# VBATTSecondary.net
KiCad netlist of a schematic drawn in Altium Designer
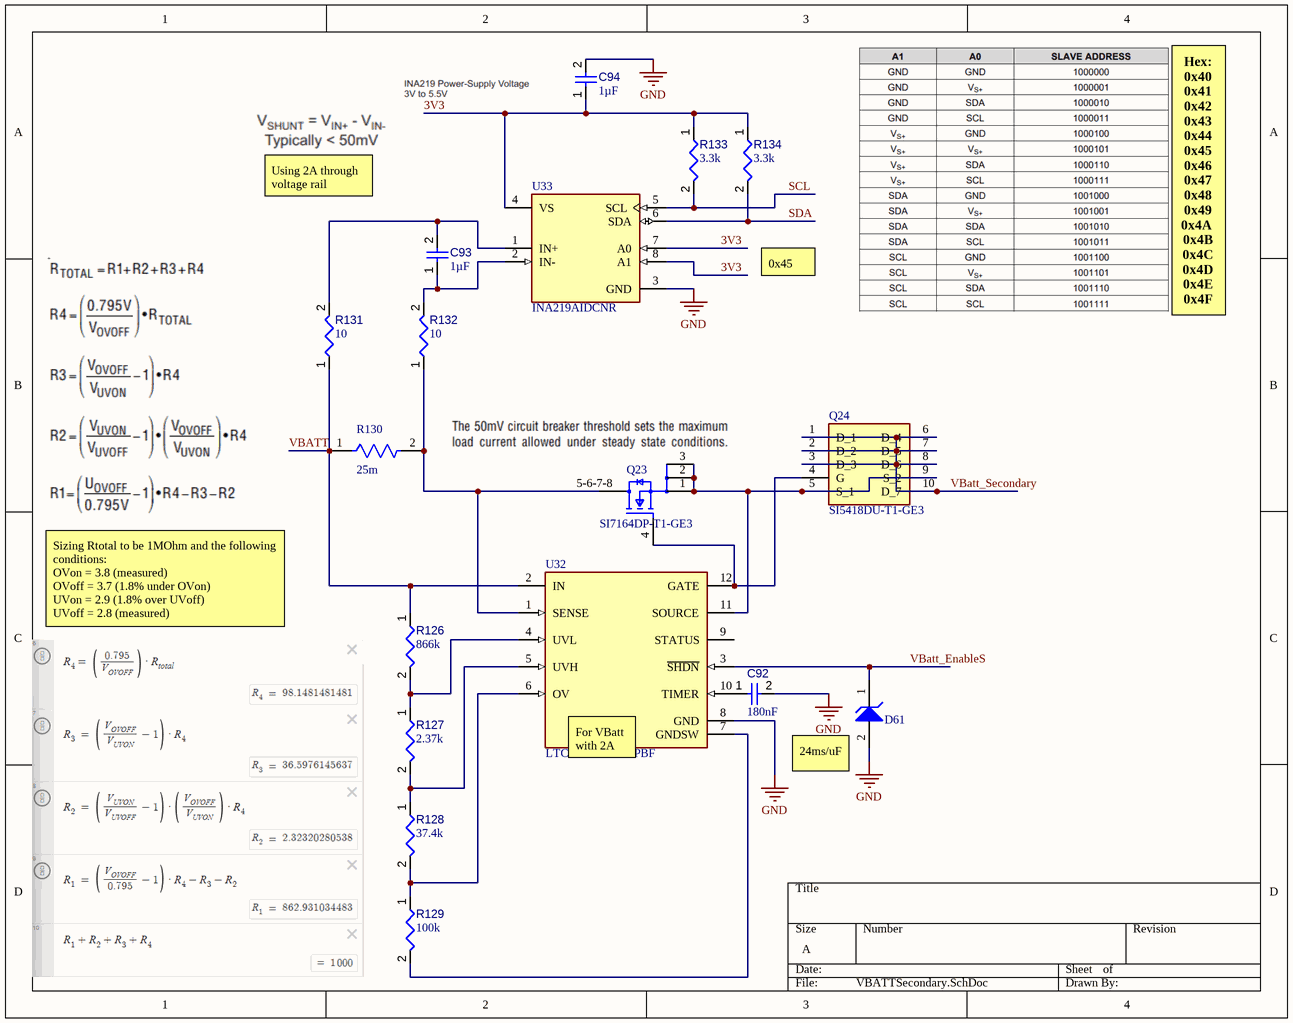
[diagram p0: VBATTSecondary.SchDoc]

(export (version "E")
  (design (tool "Eeschema 10.0.6"))
  (components
    (comp (ref "C92")
      (value "180nF")
      (footprint "FP-C0805C-DN-IPC_A")
      (fields (field (name "Comment") "C0805C184K5RACTU"))
      (libsource (lib "UGA SSRL Hardware Team") (part "CAP-NP-2"))
    )
    (comp (ref "C93")
      (value "1µF")
      (footprint "CAPC1608X90X40LL10T20")
      (description "Chip Capacitor, 1 uF, +/- 10%, 25 V, 0603 (1608 Metric)")
      (fields (field (name "TOLERANCE") "10%") (field (name "Comment") "Capacitor 1 uF +/- 10% 25 V 0603"))
      (libsource (lib "UGA SSRL Hardware Team") (part "CAP-NP-2"))
    )
    (comp (ref "C94")
      (value "1µF")
      (footprint "CAPC1608X90X35ML15T15")
      (description "Chip Capacitor, 1 uF, +/- 10%, 16 V, 0603 (1608 Metric)")
      (fields (field (name "TOLERANCE") "10%") (field (name "Comment") "Capacitor 1uF +/- 10% 16V 0603"))
      (libsource (lib "UGA SSRL Hardware Team") (part "CAP-NP-2"))
    )
    (comp (ref "D61")
      (value "MM3Z3V6T1G")
      (footprint "ONSC-SOD-323-2-477-02_V")
      (description "Zener Voltage Regulator, 300 mW, 2-Pin SOD-323, Pb-Free, Tape and Reel")
      (fields (field (name "MANUFACTURER") "On Semiconductor"))
      (libsource (lib "Altium Content Vault") (part "ONSC-K1A2-2"))
    )
    (comp (ref "Q23")
      (value "SI7164DP-T1-GE3")
      (footprint "Vishay_S17-0173-SINGLE_MFG")
      (libsource (lib "UGA SSRL Hardware Team") (part "SI7164DP-T1-GE3"))
    )
    (comp (ref "Q24")
      (value "SI5418DU-T1-GE3")
      (footprint "SI5418DU-T1-GE3-Footprint-1")
      (libsource (lib "UGA SSRL Hardware Team") (part "SI5418DU-T1-GE3-Symbol-1"))
    )
    (comp (ref "R126")
      (value "866k")
      (footprint "RESC0603X26X15NL03T05")
      (description "Fixed Resistor, Metal Glaze/thick Film, 0.05W, 866000ohm, 25V, 1% +/-Tol, -200,200ppm/Cel, 0201")
      (fields (field (name "TOLERANCE") "1%") (field (name "POWER") "50mW"))
      (libsource (lib "UGA SSRL Hardware Team") (part "RES-2"))
    )
    (comp (ref "R127")
      (value "2.37k")
      (footprint "RESC0402(1005)_L")
      (description "2K37 0.063W 1% 0402 (1005 Metric)  SMD")
      (fields (field (name "TOLERANCE") "1%") (field (name "POWER") "63mW"))
      (libsource (lib "UGA SSRL Hardware Team") (part "2D37KR2F"))
    )
    (comp (ref "R128")
      (value "37.4k")
      (footprint "FP-CR0603-IPC_A")
      (fields
        (field (name "POWER") "100mW")
        (field (name "TOLERANCE") "1%")
        (field (name "Comment") "CR0603-FX-3742ELF")
      )
      (libsource (lib "UGA SSRL Hardware Team") (part "RES-2"))
    )
    (comp (ref "R129")
      (value "100k")
      (footprint "RESC1005X40X25ML05T05")
      (description "Chip Resistor, 100 KOhm, +/- 1%, 0.1 W, -55 to 155 degC, 0402 (1005 Metric)")
      (fields (field (name "POWER") "100mW") (field (name "TOLERANCE") "1%"))
      (libsource (lib "UGA SSRL Hardware Team") (part "RES-2"))
    )
    (comp (ref "R130")
      (value "CSR1206FK25L0")
      (footprint "FP-CSR1206-IPC_C")
      (description "General Purpose Thick Film Chip Resistor, 1206, 25mΩ, 1%, 0.5W")
      (fields (field (name "RESISTANCE") "25m") (field (name "TOLERANCE") "1%"))
      (libsource (lib "Altium Content Vault") (part "1029c3af85768c4190bb7ad29bc67b5"))
    )
    (comp (ref "R131")
      (value "10")
      (footprint "RESC0402(1005)_L")
      (description "Chip Resistor, 10 Ohms, +/-1 %, 63 mW, -55 to 155 degC, 0402")
      (fields (field (name "TOLERANCE") "1%") (field (name "POWER") "63mW"))
      (libsource (lib "UGA SSRL Hardware Team") (part "RES-2"))
    )
    (comp (ref "R132")
      (value "10")
      (footprint "RESC0402(1005)_L")
      (description "Chip Resistor, 10 Ohms, +/-1 %, 63 mW, -55 to 155 degC, 0402")
      (fields (field (name "TOLERANCE") "1%") (field (name "POWER") "63mW"))
      (libsource (lib "UGA SSRL Hardware Team") (part "RES-2"))
    )
    (comp (ref "R133")
      (value "3.3k")
      (footprint "FP-CRCW1210-e3-IPC_C")
      (fields
        (field (name "TOLERANCE") "5%")
        (field (name "POWER") "500mW")
        (field (name "Comment") "CRCW12103K30JNEA")
      )
      (libsource (lib "UGA SSRL Hardware Team") (part "RES-2"))
    )
    (comp (ref "R134")
      (value "3.3k")
      (footprint "FP-CRCW1210-e3-IPC_C")
      (fields
        (field (name "TOLERANCE") "5%")
        (field (name "POWER") "500mW")
        (field (name "Comment") "CRCW12103K30JNEA")
      )
      (libsource (lib "UGA SSRL Hardware Team") (part "RES-2"))
    )
    (comp (ref "U32")
      (value "LTC4231HMS-1#PBF")
      (footprint "FP-MS-12-05-08-1668-MFG")
      (description "IC HOT SWAP CTRLR GP 12MSOP")
      (libsource (lib "Altium Content Vault") (part "22a006f8750c3b6cd4295fbd2c2f62c"))
    )
    (comp (ref "U33")
      (value "INA219AIDCNR")
      (footprint "FP-DCN0008A-IPC_A")
      (description "Power Supply Support Circuit, Fixed, 2 Channel, 2V, PDSO8")
      (libsource (lib "UGA SSRL Hardware Team") (part "e16934b8ef90d0e345b266f0ae9cd81"))
    )
  )
  (nets
    (net (code "1") (name "/3V3") (class "Default")
      (node (ref "C94") (pin "1") (pinfunction "1_1") (pintype "passive"))
      (node (ref "R133") (pin "1") (pinfunction "1_1") (pintype "passive"))
      (node (ref "R134") (pin "1") (pinfunction "1_1") (pintype "passive"))
      (node (ref "U33") (pin "4") (pinfunction "VS_4") (pintype "power_in"))
      (node (ref "U33") (pin "7") (pinfunction "A0_7") (pintype "input"))
      (node (ref "U33") (pin "8") (pinfunction "A1_8") (pintype "input"))
    )
    (net (code "2") (name "/SCL") (class "Default")
      (node (ref "R133") (pin "2") (pinfunction "2_2") (pintype "passive"))
      (node (ref "U33") (pin "5") (pinfunction "SCL_5") (pintype "input"))
    )
    (net (code "3") (name "/SDA") (class "Default")
      (node (ref "R134") (pin "2") (pinfunction "2_2") (pintype "passive"))
      (node (ref "U33") (pin "6") (pinfunction "SDA_6") (pintype "bidirectional"))
    )
    (net (code "4") (name "/VBATT") (class "Default")
      (node (ref "R126") (pin "1") (pinfunction "1_1") (pintype "passive"))
      (node (ref "R130") (pin "1") (pinfunction "1_1") (pintype "passive"))
      (node (ref "R131") (pin "1") (pinfunction "1_1") (pintype "passive"))
      (node (ref "U32") (pin "2") (pinfunction "IN_2") (pintype "power_in"))
    )
    (net (code "5") (name "/VBatt_EnableS") (class "Default")
      (node (ref "D61") (pin "1") (pinfunction "K_1") (pintype "passive"))
      (node (ref "U32") (pin "3") (pinfunction "~{SHDN}_3") (pintype "input"))
    )
    (net (code "6") (name "/VBatt_Secondary") (class "Default")
      (node (ref "Q24") (pin "1") (pinfunction "D_1_1") (pintype "passive"))
      (node (ref "Q24") (pin "10") (pinfunction "D_7_10") (pintype "passive"))
      (node (ref "Q24") (pin "2") (pinfunction "D_2_2") (pintype "passive"))
      (node (ref "Q24") (pin "3") (pinfunction "D_3_3") (pintype "passive"))
      (node (ref "Q24") (pin "6") (pinfunction "D_4_6") (pintype "passive"))
      (node (ref "Q24") (pin "7") (pinfunction "D_5_7") (pintype "passive"))
      (node (ref "Q24") (pin "8") (pinfunction "D_6_8") (pintype "passive"))
    )
    (net (code "7") (name "GND") (class "Default")
      (node (ref "C92") (pin "2") (pinfunction "2_2") (pintype "passive"))
      (node (ref "C94") (pin "2") (pinfunction "2_2") (pintype "passive"))
      (node (ref "D61") (pin "2") (pinfunction "A_2") (pintype "passive"))
      (node (ref "U32") (pin "8") (pinfunction "GND_8") (pintype "power_in"))
      (node (ref "U33") (pin "3") (pinfunction "GND_3") (pintype "power_in"))
    )
    (net (code "8") (name "Net-(Q23-D)") (class "Default")
      (node (ref "Q23") (pin "5-6-7-8") (pinfunction "D_5-6-7-8") (pintype "passive"))
      (node (ref "R130") (pin "2") (pinfunction "2_2") (pintype "passive"))
      (node (ref "R132") (pin "1") (pinfunction "1_1") (pintype "passive"))
      (node (ref "U32") (pin "1") (pinfunction "SENSE_1") (pintype "input"))
    )
    (net (code "9") (name "Net-(Q23-G)") (class "Default")
      (node (ref "Q23") (pin "4") (pinfunction "G_4") (pintype "passive"))
      (node (ref "Q24") (pin "4") (pinfunction "G_4") (pintype "passive"))
      (node (ref "U32") (pin "12") (pinfunction "GATE_12") (pintype "passive"))
    )
    (net (code "10") (name "Net-(Q24-S_1)") (class "Default")
      (node (ref "Q23") (pin "1") (pinfunction "S_1") (pintype "passive"))
      (node (ref "Q23") (pin "2") (pinfunction "S_2") (pintype "passive"))
      (node (ref "Q23") (pin "3") (pinfunction "S_3") (pintype "passive"))
      (node (ref "Q24") (pin "5") (pinfunction "S_1_5") (pintype "passive"))
      (node (ref "Q24") (pin "9") (pinfunction "S_2_9") (pintype "passive"))
      (node (ref "U32") (pin "11") (pinfunction "SOURCE_11") (pintype "passive"))
    )
    (net (code "11") (name "Net-(U32-GNDSW)") (class "Default")
      (node (ref "R129") (pin "2") (pinfunction "2_2") (pintype "passive"))
      (node (ref "U32") (pin "7") (pinfunction "GNDSW_7") (pintype "power_in"))
    )
    (net (code "12") (name "Net-(U32-OV)") (class "Default")
      (node (ref "R128") (pin "2") (pinfunction "2_2") (pintype "passive"))
      (node (ref "R129") (pin "1") (pinfunction "1_1") (pintype "passive"))
      (node (ref "U32") (pin "6") (pinfunction "OV_6") (pintype "input"))
    )
    (net (code "13") (name "Net-(U32-TIMER)") (class "Default")
      (node (ref "C92") (pin "1") (pinfunction "1_1") (pintype "passive"))
      (node (ref "U32") (pin "10") (pinfunction "TIMER_10") (pintype "input"))
    )
    (net (code "14") (name "Net-(U32-UVH)") (class "Default")
      (node (ref "R127") (pin "2") (pinfunction "2_2") (pintype "passive"))
      (node (ref "R128") (pin "1") (pinfunction "1_1") (pintype "passive"))
      (node (ref "U32") (pin "5") (pinfunction "UVH_5") (pintype "input"))
    )
    (net (code "15") (name "Net-(U32-UVL)") (class "Default")
      (node (ref "R126") (pin "2") (pinfunction "2_2") (pintype "passive"))
      (node (ref "R127") (pin "1") (pinfunction "1_1") (pintype "passive"))
      (node (ref "U32") (pin "4") (pinfunction "UVL_4") (pintype "input"))
    )
    (net (code "16") (name "Net-(U33-IN+)") (class "Default")
      (node (ref "C93") (pin "2") (pinfunction "2_2") (pintype "passive"))
      (node (ref "R131") (pin "2") (pinfunction "2_2") (pintype "passive"))
      (node (ref "U33") (pin "1") (pinfunction "IN+_1") (pintype "passive"))
    )
    (net (code "17") (name "Net-(U33-IN-)") (class "Default")
      (node (ref "C93") (pin "1") (pinfunction "1_1") (pintype "passive"))
      (node (ref "R132") (pin "2") (pinfunction "2_2") (pintype "passive"))
      (node (ref "U33") (pin "2") (pinfunction "IN-_2") (pintype "input"))
    )
    (net (code "18") (name "unconnected-(U32-STATUS-Pad9)") (class "Default")
      (node (ref "U32") (pin "9") (pinfunction "STATUS_9") (pintype "open_collector"))
    )
  )
)
